# dual_power_supply.net
KiCad netlist of a schematic drawn in EAGLE
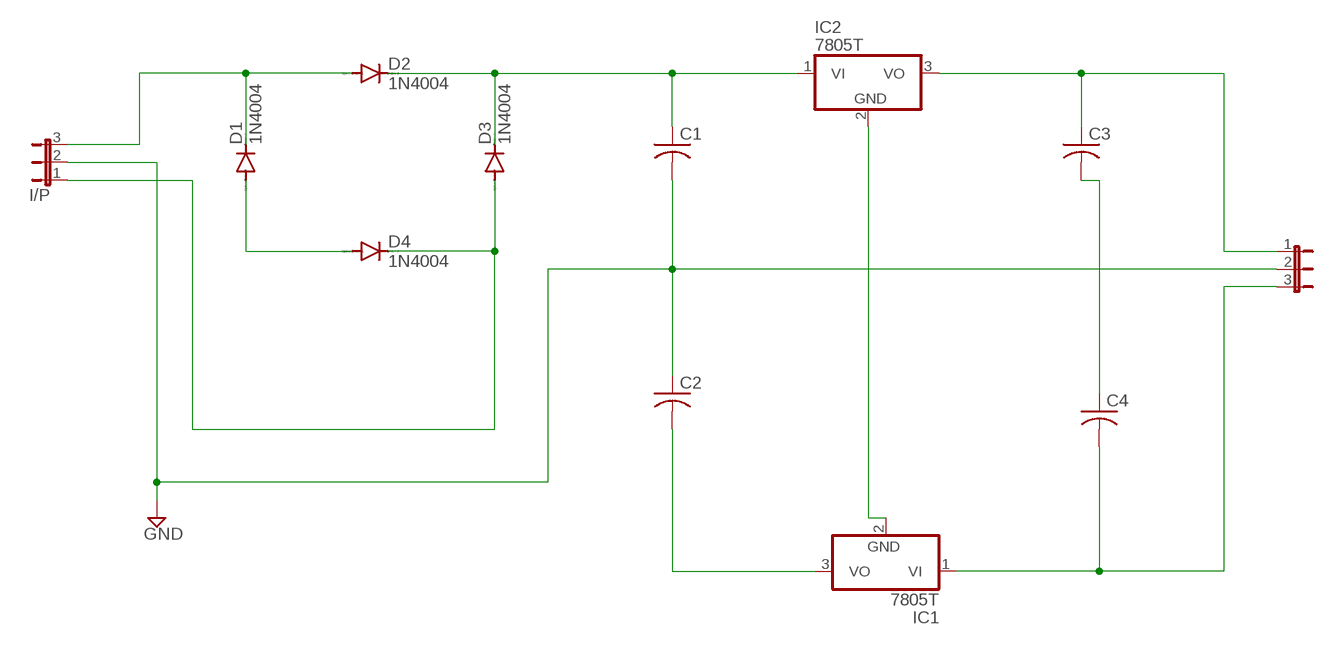
[diagram p0: schematic, sheet 1]

(export (version "E")
  (design (tool "Eeschema 10.0.6"))
  (components
    (comp (ref "C1")
      (value "C-US025-024X044")
      (footprint "eagle-import:C025-024X044")
      (libsource (lib "eagle-import") (part "C-US025-024X044"))
    )
    (comp (ref "C2")
      (value "C-US025-024X044")
      (footprint "eagle-import:C025-024X044")
      (libsource (lib "eagle-import") (part "C-US025-024X044"))
    )
    (comp (ref "C3")
      (value "C-US025-024X044")
      (footprint "eagle-import:C025-024X044")
      (libsource (lib "eagle-import") (part "C-US025-024X044"))
    )
    (comp (ref "C4")
      (value "C-US025-024X044")
      (footprint "eagle-import:C025-024X044")
      (libsource (lib "eagle-import") (part "C-US025-024X044"))
    )
    (comp (ref "D1")
      (value "1N4004")
      (footprint "eagle-import:DO41-10")
      (libsource (lib "eagle-import") (part "1N4004"))
    )
    (comp (ref "D2")
      (value "1N4004")
      (footprint "eagle-import:DO41-10")
      (libsource (lib "eagle-import") (part "1N4004"))
    )
    (comp (ref "D3")
      (value "1N4004")
      (footprint "eagle-import:DO41-10")
      (libsource (lib "eagle-import") (part "1N4004"))
    )
    (comp (ref "D4")
      (value "1N4004")
      (footprint "eagle-import:DO41-10")
      (libsource (lib "eagle-import") (part "1N4004"))
    )
    (comp (ref "I/P")
      (value "JP2E")
      (footprint "eagle-import:JP2")
      (libsource (lib "eagle-import") (part "JP2E"))
    )
    (comp (ref "IC1")
      (value "7805T")
      (footprint "eagle-import:TO220H")
      (libsource (lib "eagle-import") (part "78T05"))
    )
    (comp (ref "IC2")
      (value "7805T")
      (footprint "eagle-import:TO220H")
      (libsource (lib "eagle-import") (part "78T05"))
    )
    (comp (ref "O/P")
      (value "JP2E")
      (footprint "eagle-import:JP2")
      (libsource (lib "eagle-import") (part "JP2E"))
    )
  )
  (nets
    (net (code "1") (name "GND") (class "Default")
      (node (ref "C1") (pin "2") (pinfunction "2_2") (pintype "passive"))
      (node (ref "C2") (pin "1") (pinfunction "1_1") (pintype "passive"))
      (node (ref "I/P") (pin "2") (pinfunction "2_2") (pintype "passive"))
      (node (ref "O/P") (pin "2") (pinfunction "2_2") (pintype "passive"))
    )
    (net (code "2") (name "Net-(C3-Pad2)") (class "Default")
      (node (ref "C3") (pin "2") (pinfunction "2_2") (pintype "passive"))
      (node (ref "C4") (pin "1") (pinfunction "1_1") (pintype "passive"))
    )
    (net (code "3") (name "Net-(D1-PadA)") (class "Default")
      (node (ref "D1") (pin "A") (pinfunction "A_A") (pintype "passive"))
      (node (ref "D4") (pin "A") (pinfunction "A_A") (pintype "passive"))
    )
    (net (code "4") (name "Net-(D1-PadC)") (class "Default")
      (node (ref "D1") (pin "C") (pinfunction "C_C") (pintype "passive"))
      (node (ref "D2") (pin "A") (pinfunction "A_A") (pintype "passive"))
      (node (ref "I/P") (pin "3") (pinfunction "3_3") (pintype "passive"))
    )
    (net (code "5") (name "Net-(D3-PadA)") (class "Default")
      (node (ref "D3") (pin "A") (pinfunction "A_A") (pintype "passive"))
      (node (ref "D4") (pin "C") (pinfunction "C_C") (pintype "passive"))
      (node (ref "I/P") (pin "1") (pinfunction "1_1") (pintype "passive"))
    )
    (net (code "6") (name "Net-(IC1-GND)") (class "Default")
      (node (ref "IC1") (pin "2") (pinfunction "GND_2") (pintype "passive"))
      (node (ref "IC2") (pin "2") (pinfunction "GND_2") (pintype "passive"))
    )
    (net (code "7") (name "Net-(IC1-VI)") (class "Default")
      (node (ref "C4") (pin "2") (pinfunction "2_2") (pintype "passive"))
      (node (ref "IC1") (pin "1") (pinfunction "VI_1") (pintype "input"))
      (node (ref "O/P") (pin "3") (pinfunction "3_3") (pintype "passive"))
    )
    (net (code "8") (name "Net-(IC1-VO)") (class "Default")
      (node (ref "C2") (pin "2") (pinfunction "2_2") (pintype "passive"))
      (node (ref "IC1") (pin "3") (pinfunction "VO_3") (pintype "passive"))
    )
    (net (code "9") (name "Net-(IC2-VI)") (class "Default")
      (node (ref "C1") (pin "1") (pinfunction "1_1") (pintype "passive"))
      (node (ref "D2") (pin "C") (pinfunction "C_C") (pintype "passive"))
      (node (ref "D3") (pin "C") (pinfunction "C_C") (pintype "passive"))
      (node (ref "IC2") (pin "1") (pinfunction "VI_1") (pintype "input"))
    )
    (net (code "10") (name "Net-(IC2-VO)") (class "Default")
      (node (ref "C3") (pin "1") (pinfunction "1_1") (pintype "passive"))
      (node (ref "IC2") (pin "3") (pinfunction "VO_3") (pintype "passive"))
      (node (ref "O/P") (pin "1") (pinfunction "1_1") (pintype "passive"))
    )
  )
)
